# HelvePicV1_1SMDbb.net
KiCad netlist of a schematic drawn in EAGLE
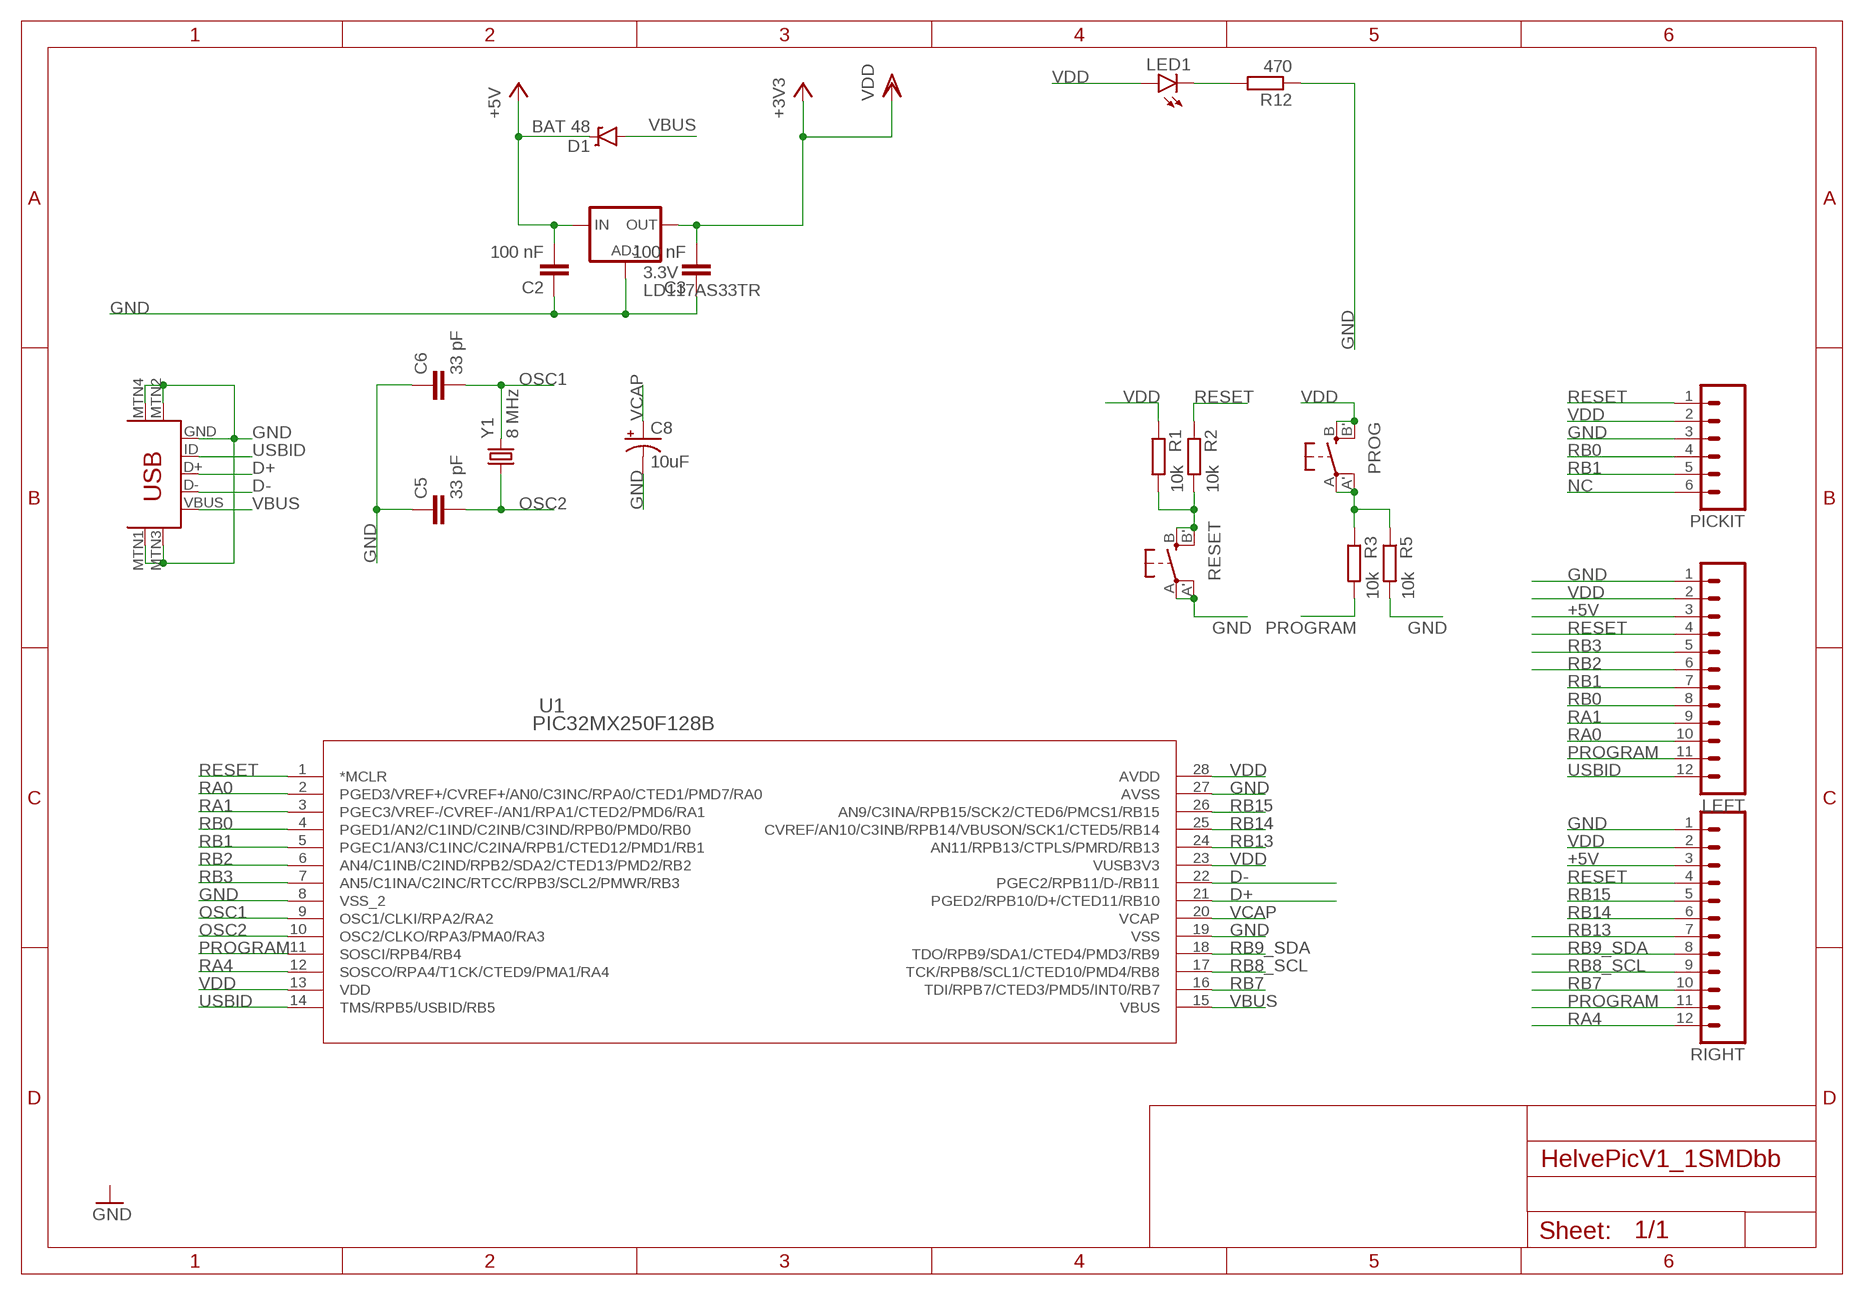
[diagram p0: schematic, sheet 1]

(export (version "E")
  (design (tool "Eeschema 10.0.6"))
  (components
    (comp (ref "3.3V")
      (value "LD117AS33TR")
      (footprint "eagle-import:SOT223")
      (libsource (lib "eagle-import") (part "LD117A?S33TR"))
    )
    (comp (ref "C2")
      (value "100 nF")
      (footprint "eagle-import:0805")
      (libsource (lib "eagle-import") (part "CAP0805"))
    )
    (comp (ref "C3")
      (value "100 nF")
      (footprint "eagle-import:0805")
      (libsource (lib "eagle-import") (part "CAP0805"))
    )
    (comp (ref "C5")
      (value "33 pF")
      (footprint "eagle-import:0805")
      (libsource (lib "eagle-import") (part "CAP0805"))
    )
    (comp (ref "C6")
      (value "33 pF")
      (footprint "eagle-import:0805")
      (libsource (lib "eagle-import") (part "CAP0805"))
    )
    (comp (ref "C8")
      (value "10uF")
      (footprint "eagle-import:EIA3216")
      (libsource (lib "eagle-import") (part "10UF-16V-10%(TANT)"))
    )
    (comp (ref "D1")
      (value "BAT 48")
      (footprint "eagle-import:SMB-DIODE")
      (libsource (lib "eagle-import") (part "DIODE-ZENERSMB"))
    )
    (comp (ref "LED1")
      (value "LED1206")
      (footprint "eagle-import:LED-1206")
      (libsource (lib "eagle-import") (part "LED1206"))
    )
    (comp (ref "LEFT")
      (value "M12PTH")
      (footprint "eagle-import:1X12")
      (libsource (lib "eagle-import") (part "M12PTH"))
    )
    (comp (ref "PICKIT")
      (value "M06LOCK")
      (footprint "eagle-import:1X06_LOCK")
      (libsource (lib "eagle-import") (part "M06LOCK"))
    )
    (comp (ref "PROG")
      (value "SPST_TACT-EVQQ2")
      (footprint "eagle-import:EVQ-Q2")
      (libsource (lib "eagle-import") (part "SPST_TACT-EVQQ2"))
    )
    (comp (ref "R1")
      (value "10k")
      (footprint "eagle-import:M0805")
      (libsource (lib "eagle-import") (part "R-EU_M0805"))
    )
    (comp (ref "R2")
      (value "10k")
      (footprint "eagle-import:M0805")
      (libsource (lib "eagle-import") (part "R-EU_M0805"))
    )
    (comp (ref "R3")
      (value "10k")
      (footprint "eagle-import:M0805")
      (libsource (lib "eagle-import") (part "R-EU_M0805"))
    )
    (comp (ref "R5")
      (value "10k")
      (footprint "eagle-import:M0805")
      (libsource (lib "eagle-import") (part "R-EU_M0805"))
    )
    (comp (ref "R12")
      (value "470")
      (footprint "eagle-import:M0805")
      (libsource (lib "eagle-import") (part "R-EU_M0805"))
    )
    (comp (ref "RESET")
      (value "SPST_TACT-EVQQ2")
      (footprint "eagle-import:EVQ-Q2")
      (libsource (lib "eagle-import") (part "SPST_TACT-EVQQ2"))
    )
    (comp (ref "RIGHT")
      (value "M12PTH")
      (footprint "eagle-import:1X12")
      (libsource (lib "eagle-import") (part "M12PTH"))
    )
    (comp (ref "U$2")
      (value "USB-MINIB-5PIN")
      (footprint "eagle-import:USB-MINIB")
      (libsource (lib "eagle-import") (part "USB-MINIB-5PIN"))
    )
    (comp (ref "U1")
      (value "PIC32MX250F128B")
      (footprint "eagle-import:SOIC28-W_MC")
      (libsource (lib "eagle-import") (part "PIC32MX250F128B-I_SO"))
    )
    (comp (ref "Y1")
      (value "8 MHz")
      (footprint "eagle-import:HC49UP")
      (libsource (lib "eagle-import") (part "CRYSTALSMD"))
    )
  )
  (nets
    (net (code "1") (name "+3V3") (class "Default")
      (node (ref "3.3V") (pin "4") (pinfunction "OUT_4") (pintype "passive"))
      (node (ref "C3") (pin "2") (pinfunction "2_2") (pintype "passive"))
      (node (ref "LED1") (pin "A") (pinfunction "A_A") (pintype "passive"))
      (node (ref "LEFT") (pin "2") (pinfunction "2_2") (pintype "passive"))
      (node (ref "PICKIT") (pin "2") (pinfunction "2_2") (pintype "passive"))
      (node (ref "PROG") (pin "B") (pinfunction "S_B") (pintype "passive"))
      (node (ref "PROG") (pin "B'") (pinfunction "S1_B'") (pintype "passive"))
      (node (ref "R1") (pin "1") (pinfunction "1_1") (pintype "passive"))
      (node (ref "RIGHT") (pin "2") (pinfunction "2_2") (pintype "passive"))
      (node (ref "U1") (pin "13") (pinfunction "VDD_13") (pintype "power_in"))
      (node (ref "U1") (pin "23") (pinfunction "VUSB3V3_23") (pintype "power_in"))
      (node (ref "U1") (pin "28") (pinfunction "AVDD_28") (pintype "power_in"))
    )
    (net (code "2") (name "+5V") (class "Default")
      (node (ref "3.3V") (pin "3") (pinfunction "IN_3") (pintype "input"))
      (node (ref "C2") (pin "2") (pinfunction "2_2") (pintype "passive"))
      (node (ref "D1") (pin "C") (pinfunction "C_C") (pintype "passive"))
      (node (ref "LEFT") (pin "3") (pinfunction "3_3") (pintype "passive"))
      (node (ref "RIGHT") (pin "3") (pinfunction "3_3") (pintype "passive"))
    )
    (net (code "3") (name "/D+") (class "Default")
      (node (ref "U$2") (pin "D+") (pinfunction "D+_D+") (pintype "bidirectional"))
      (node (ref "U1") (pin "21") (pinfunction "PGED2/RPB10/D+/CTED11/RB10_21") (pintype "bidirectional"))
    )
    (net (code "4") (name "/D-") (class "Default")
      (node (ref "U$2") (pin "D-") (pinfunction "D-_D-") (pintype "bidirectional"))
      (node (ref "U1") (pin "22") (pinfunction "PGEC2/RPB11/D-/RB11_22") (pintype "bidirectional"))
    )
    (net (code "5") (name "/NC") (class "Default")
      (node (ref "PICKIT") (pin "6") (pinfunction "6_6") (pintype "passive"))
    )
    (net (code "6") (name "/OSC1") (class "Default")
      (node (ref "C6") (pin "2") (pinfunction "2_2") (pintype "passive"))
      (node (ref "U1") (pin "9") (pinfunction "OSC1/CLKI/RPA2/RA2_9") (pintype "bidirectional"))
      (node (ref "Y1") (pin "2") (pinfunction "2_2") (pintype "passive"))
    )
    (net (code "7") (name "/OSC2") (class "Default")
      (node (ref "C5") (pin "2") (pinfunction "2_2") (pintype "passive"))
      (node (ref "U1") (pin "10") (pinfunction "OSC2/CLKO/RPA3/PMA0/RA3_10") (pintype "bidirectional"))
      (node (ref "Y1") (pin "1") (pinfunction "1_1") (pintype "passive"))
    )
    (net (code "8") (name "/PROGRAM") (class "Default")
      (node (ref "LEFT") (pin "11") (pinfunction "11_11") (pintype "passive"))
      (node (ref "R3") (pin "2") (pinfunction "2_2") (pintype "passive"))
      (node (ref "RIGHT") (pin "11") (pinfunction "11_11") (pintype "passive"))
      (node (ref "U1") (pin "11") (pinfunction "SOSCI/RPB4/RB4_11") (pintype "bidirectional"))
    )
    (net (code "9") (name "/RA0") (class "Default")
      (node (ref "LEFT") (pin "10") (pinfunction "10_10") (pintype "passive"))
      (node (ref "U1") (pin "2") (pinfunction "PGED3/VREF+/CVREF+/AN0/C3INC/RPA0/CTED1/PMD7/RA0_2") (pintype "bidirectional"))
    )
    (net (code "10") (name "/RA1") (class "Default")
      (node (ref "LEFT") (pin "9") (pinfunction "9_9") (pintype "passive"))
      (node (ref "U1") (pin "3") (pinfunction "PGEC3/VREF-/CVREF-/AN1/RPA1/CTED2/PMD6/RA1_3") (pintype "bidirectional"))
    )
    (net (code "11") (name "/RA4") (class "Default")
      (node (ref "RIGHT") (pin "12") (pinfunction "12_12") (pintype "passive"))
      (node (ref "U1") (pin "12") (pinfunction "SOSCO/RPA4/T1CK/CTED9/PMA1/RA4_12") (pintype "bidirectional"))
    )
    (net (code "12") (name "/RB0") (class "Default")
      (node (ref "LEFT") (pin "8") (pinfunction "8_8") (pintype "passive"))
      (node (ref "PICKIT") (pin "4") (pinfunction "4_4") (pintype "passive"))
      (node (ref "U1") (pin "4") (pinfunction "PGED1/AN2/C1IND/C2INB/C3IND/RPB0/PMD0/RB0_4") (pintype "bidirectional"))
    )
    (net (code "13") (name "/RB1") (class "Default")
      (node (ref "LEFT") (pin "7") (pinfunction "7_7") (pintype "passive"))
      (node (ref "PICKIT") (pin "5") (pinfunction "5_5") (pintype "passive"))
      (node (ref "U1") (pin "5") (pinfunction "PGEC1/AN3/C1INC/C2INA/RPB1/CTED12/PMD1/RB1_5") (pintype "bidirectional"))
    )
    (net (code "14") (name "/RB2") (class "Default")
      (node (ref "LEFT") (pin "6") (pinfunction "6_6") (pintype "passive"))
      (node (ref "U1") (pin "6") (pinfunction "AN4/C1INB/C2IND/RPB2/SDA2/CTED13/PMD2/RB2_6") (pintype "bidirectional"))
    )
    (net (code "15") (name "/RB3") (class "Default")
      (node (ref "LEFT") (pin "5") (pinfunction "5_5") (pintype "passive"))
      (node (ref "U1") (pin "7") (pinfunction "AN5/C1INA/C2INC/RTCC/RPB3/SCL2/PMWR/RB3_7") (pintype "bidirectional"))
    )
    (net (code "16") (name "/RB7") (class "Default")
      (node (ref "RIGHT") (pin "10") (pinfunction "10_10") (pintype "passive"))
      (node (ref "U1") (pin "16") (pinfunction "TDI/RPB7/CTED3/PMD5/INT0/RB7_16") (pintype "bidirectional"))
    )
    (net (code "17") (name "/RB8_SCL") (class "Default")
      (node (ref "RIGHT") (pin "9") (pinfunction "9_9") (pintype "passive"))
      (node (ref "U1") (pin "17") (pinfunction "TCK/RPB8/SCL1/CTED10/PMD4/RB8_17") (pintype "bidirectional"))
    )
    (net (code "18") (name "/RB9_SDA") (class "Default")
      (node (ref "RIGHT") (pin "8") (pinfunction "8_8") (pintype "passive"))
      (node (ref "U1") (pin "18") (pinfunction "TDO/RPB9/SDA1/CTED4/PMD3/RB9_18") (pintype "bidirectional"))
    )
    (net (code "19") (name "/RB13") (class "Default")
      (node (ref "RIGHT") (pin "7") (pinfunction "7_7") (pintype "passive"))
      (node (ref "U1") (pin "24") (pinfunction "AN11/RPB13/CTPLS/PMRD/RB13_24") (pintype "bidirectional"))
    )
    (net (code "20") (name "/RB14") (class "Default")
      (node (ref "RIGHT") (pin "6") (pinfunction "6_6") (pintype "passive"))
      (node (ref "U1") (pin "25") (pinfunction "CVREF/AN10/C3INB/RPB14/VBUSON/SCK1/CTED5/RB14_25") (pintype "bidirectional"))
    )
    (net (code "21") (name "/RB15") (class "Default")
      (node (ref "RIGHT") (pin "5") (pinfunction "5_5") (pintype "passive"))
      (node (ref "U1") (pin "26") (pinfunction "AN9/C3INA/RPB15/SCK2/CTED6/PMCS1/RB15_26") (pintype "bidirectional"))
    )
    (net (code "22") (name "/RESET") (class "Default")
      (node (ref "LEFT") (pin "4") (pinfunction "4_4") (pintype "passive"))
      (node (ref "PICKIT") (pin "1") (pinfunction "1_1") (pintype "passive"))
      (node (ref "R2") (pin "1") (pinfunction "1_1") (pintype "passive"))
      (node (ref "RIGHT") (pin "4") (pinfunction "4_4") (pintype "passive"))
      (node (ref "U1") (pin "1") (pinfunction "*MCLR_1") (pintype "input"))
    )
    (net (code "23") (name "/USBID") (class "Default")
      (node (ref "LEFT") (pin "12") (pinfunction "12_12") (pintype "passive"))
      (node (ref "U$2") (pin "ID") (pinfunction "ID_ID") (pintype "bidirectional"))
      (node (ref "U1") (pin "14") (pinfunction "TMS/RPB5/USBID/RB5_14") (pintype "bidirectional"))
    )
    (net (code "24") (name "/VBUS") (class "Default")
      (node (ref "D1") (pin "A") (pinfunction "A_A") (pintype "passive"))
      (node (ref "U$2") (pin "VBUS") (pinfunction "VBUS_VBUS") (pintype "bidirectional"))
      (node (ref "U1") (pin "15") (pinfunction "VBUS_15") (pintype "power_in"))
    )
    (net (code "25") (name "/VCAP") (class "Default")
      (node (ref "C8") (pin "A") (pinfunction "+_A") (pintype "passive"))
      (node (ref "U1") (pin "20") (pinfunction "VCAP_20") (pintype "power_in"))
    )
    (net (code "26") (name "GND") (class "Default")
      (node (ref "3.3V") (pin "1") (pinfunction "ADJ_1") (pintype "input"))
      (node (ref "C2") (pin "1") (pinfunction "1_1") (pintype "passive"))
      (node (ref "C3") (pin "1") (pinfunction "1_1") (pintype "passive"))
      (node (ref "C5") (pin "1") (pinfunction "1_1") (pintype "passive"))
      (node (ref "C6") (pin "1") (pinfunction "1_1") (pintype "passive"))
      (node (ref "C8") (pin "C") (pinfunction "-_C") (pintype "passive"))
      (node (ref "LEFT") (pin "1") (pinfunction "1_1") (pintype "passive"))
      (node (ref "PICKIT") (pin "3") (pinfunction "3_3") (pintype "passive"))
      (node (ref "R12") (pin "1") (pinfunction "1_1") (pintype "passive"))
      (node (ref "R5") (pin "2") (pinfunction "2_2") (pintype "passive"))
      (node (ref "RESET") (pin "A") (pinfunction "P_A") (pintype "passive"))
      (node (ref "RESET") (pin "A'") (pinfunction "P1_A'") (pintype "passive"))
      (node (ref "RIGHT") (pin "1") (pinfunction "1_1") (pintype "passive"))
      (node (ref "U$2") (pin "GND") (pinfunction "GND_GND") (pintype "bidirectional"))
      (node (ref "U$2") (pin "MTN1") (pinfunction "MTN2_MTN1") (pintype "bidirectional"))
      (node (ref "U$2") (pin "MTN2") (pinfunction "MTN3_MTN2") (pintype "bidirectional"))
      (node (ref "U$2") (pin "MTN3") (pinfunction "MTN1_MTN3") (pintype "bidirectional"))
      (node (ref "U$2") (pin "MTN4") (pinfunction "MTN4_MTN4") (pintype "bidirectional"))
      (node (ref "U1") (pin "19") (pinfunction "VSS_19") (pintype "power_in"))
      (node (ref "U1") (pin "27") (pinfunction "AVSS_27") (pintype "power_in"))
      (node (ref "U1") (pin "8") (pinfunction "VSS_2_8") (pintype "power_in"))
    )
    (net (code "27") (name "Net-(LED1-PadC)") (class "Default")
      (node (ref "LED1") (pin "C") (pinfunction "C_C") (pintype "passive"))
      (node (ref "R12") (pin "2") (pinfunction "2_2") (pintype "passive"))
    )
    (net (code "28") (name "Net-(PROG-P)") (class "Default")
      (node (ref "PROG") (pin "A") (pinfunction "P_A") (pintype "passive"))
      (node (ref "PROG") (pin "A'") (pinfunction "P1_A'") (pintype "passive"))
      (node (ref "R3") (pin "1") (pinfunction "1_1") (pintype "passive"))
      (node (ref "R5") (pin "1") (pinfunction "1_1") (pintype "passive"))
    )
    (net (code "29") (name "Net-(RESET-S)") (class "Default")
      (node (ref "R1") (pin "2") (pinfunction "2_2") (pintype "passive"))
      (node (ref "R2") (pin "2") (pinfunction "2_2") (pintype "passive"))
      (node (ref "RESET") (pin "B") (pinfunction "S_B") (pintype "passive"))
      (node (ref "RESET") (pin "B'") (pinfunction "S1_B'") (pintype "passive"))
    )
  )
)
